# Righ_CH.net
KiCad netlist of a schematic drawn in Altium Designer
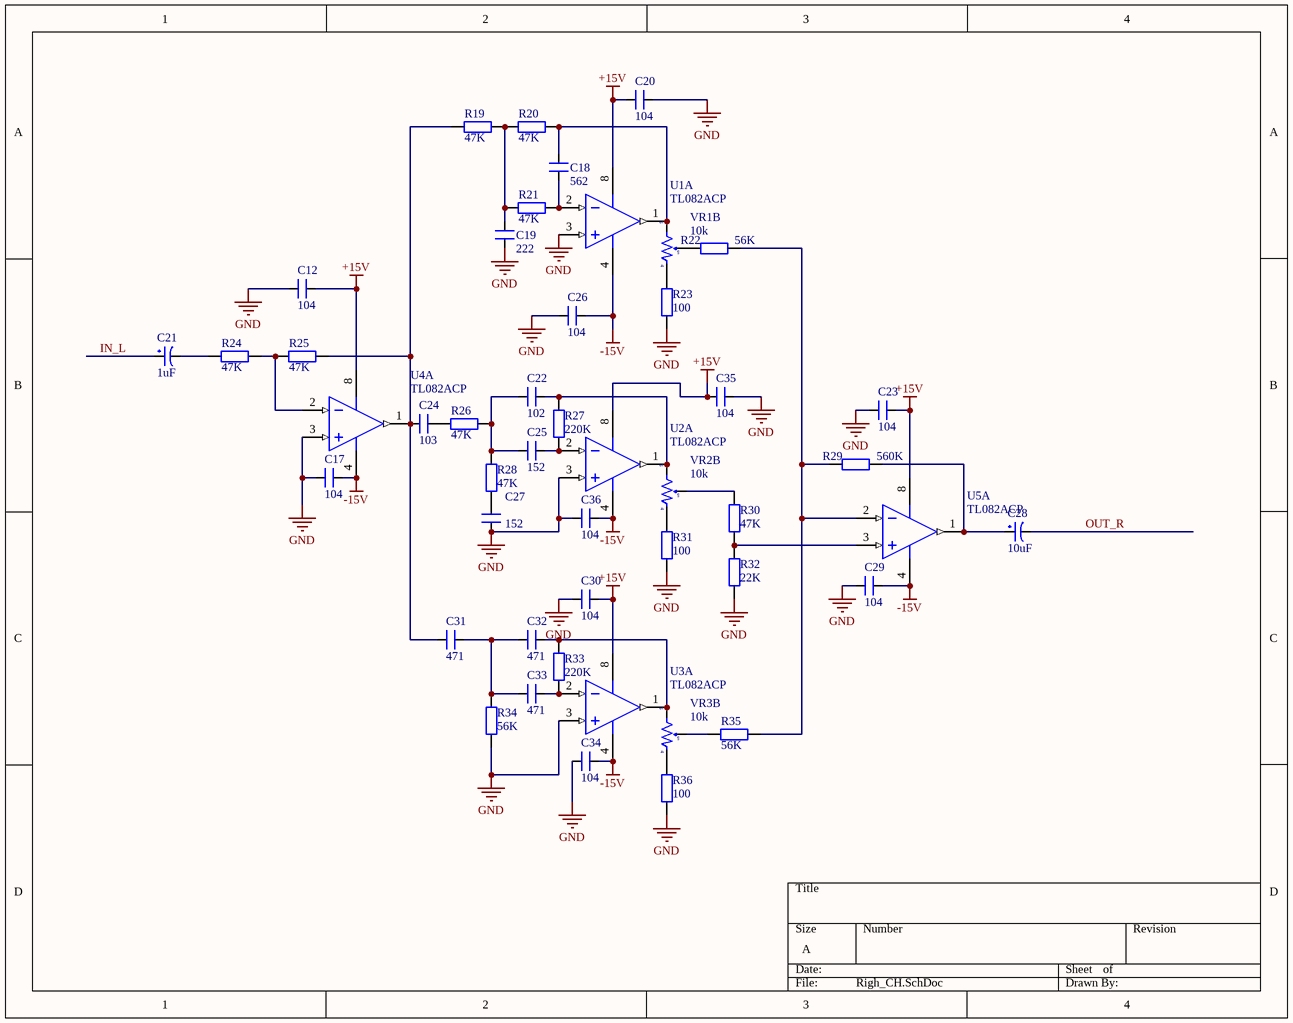
[diagram p0: Righ_CH.SchDoc]

(export (version "E")
  (design (tool "Eeschema 10.0.6"))
  (components
    (comp (ref "C12")
      (value "104")
      (footprint "TU_GOM(104-->105pF)")
      (libsource (lib "MH_DA_THU_VIEN_16122016") (part "TU_MICA_ 104 100V(2A104J)_MH"))
    )
    (comp (ref "C17")
      (value "104")
      (footprint "TU_GOM(104-->105pF)")
      (libsource (lib "MH_DA_THU_VIEN_16122016") (part "TU_MICA_ 104 100V(2A104J)_MH"))
    )
    (comp (ref "C18")
      (value "562")
      (footprint "WIMA-FKP-2-1nF")
      (libsource (lib "MH_DA_THU_VIEN_16122016") (part "TU_MICA_ 104 100V(2A104J)_MH"))
    )
    (comp (ref "C19")
      (value "222")
      (footprint "WIMA-FKP-2-1nF")
      (libsource (lib "MH_DA_THU_VIEN_16122016") (part "TU_MICA_ 104 100V(2A104J)_MH"))
    )
    (comp (ref "C20")
      (value "104")
      (footprint "TU_GOM(104-->105pF)")
      (libsource (lib "MH_DA_THU_VIEN_16122016") (part "TU_MICA_ 104 100V(2A104J)_MH"))
    )
    (comp (ref "C21")
      (value "1uF")
      (footprint "CP1/3.0")
      (description "TU_HOA_4.7uF_100V_MH")
      (libsource (lib "MH_DA_THU_VIEN_16122016") (part "TU_HOA_4.7uF_100V_MH"))
    )
    (comp (ref "C22")
      (value "102")
      (footprint "WIMA-FKP-2-1nF")
      (libsource (lib "MH_DA_THU_VIEN_16122016") (part "TU_MICA_ 104 100V(2A104J)_MH"))
    )
    (comp (ref "C23")
      (value "104")
      (footprint "TU_GOM(104-->105pF)")
      (libsource (lib "MH_DA_THU_VIEN_16122016") (part "TU_MICA_ 104 100V(2A104J)_MH"))
    )
    (comp (ref "C24")
      (value "103")
      (footprint "WIMA-FKP-2-1nF")
      (libsource (lib "MH_DA_THU_VIEN_16122016") (part "TU_MICA_ 104 100V(2A104J)_MH"))
    )
    (comp (ref "C25")
      (value "152")
      (footprint "WIMA-FKP-2-1nF")
      (libsource (lib "MH_DA_THU_VIEN_16122016") (part "TU_MICA_ 104 100V(2A104J)_MH"))
    )
    (comp (ref "C26")
      (value "104")
      (footprint "TU_GOM(104-->105pF)")
      (libsource (lib "MH_DA_THU_VIEN_16122016") (part "TU_MICA_ 104 100V(2A104J)_MH"))
    )
    (comp (ref "C27")
      (value "152")
      (footprint "WIMA-FKP-2-1nF")
      (libsource (lib "MH_DA_THU_VIEN_16122016") (part "TU_MICA_ 104 100V(2A104J)_MH"))
    )
    (comp (ref "C28")
      (value "10uF")
      (footprint "CP1/3.0")
      (description "TU_HOA_4.7uF_100V_MH")
      (libsource (lib "MH_DA_THU_VIEN_16122016") (part "TU_HOA_4.7uF_100V_MH"))
    )
    (comp (ref "C29")
      (value "104")
      (footprint "TU_GOM(104-->105pF)")
      (libsource (lib "MH_DA_THU_VIEN_16122016") (part "TU_MICA_ 104 100V(2A104J)_MH"))
    )
    (comp (ref "C30")
      (value "104")
      (footprint "TU_GOM(104-->105pF)")
      (libsource (lib "MH_DA_THU_VIEN_16122016") (part "TU_MICA_ 104 100V(2A104J)_MH"))
    )
    (comp (ref "C31")
      (value "471")
      (footprint "WIMA-FKP-2-1nF")
      (libsource (lib "MH_DA_THU_VIEN_16122016") (part "TU_MICA_ 104 100V(2A104J)_MH"))
    )
    (comp (ref "C32")
      (value "471")
      (footprint "WIMA-FKP-2-1nF")
      (libsource (lib "MH_DA_THU_VIEN_16122016") (part "TU_MICA_ 104 100V(2A104J)_MH"))
    )
    (comp (ref "C33")
      (value "471")
      (footprint "WIMA-FKP-2-1nF")
      (libsource (lib "MH_DA_THU_VIEN_16122016") (part "TU_MICA_ 104 100V(2A104J)_MH"))
    )
    (comp (ref "C34")
      (value "104")
      (footprint "TU_GOM(104-->105pF)")
      (libsource (lib "MH_DA_THU_VIEN_16122016") (part "TU_MICA_ 104 100V(2A104J)_MH"))
    )
    (comp (ref "C35")
      (value "104")
      (footprint "TU_GOM(104-->105pF)")
      (libsource (lib "MH_DA_THU_VIEN_16122016") (part "TU_MICA_ 104 100V(2A104J)_MH"))
    )
    (comp (ref "C36")
      (value "104")
      (footprint "TU_GOM(104-->105pF)")
      (libsource (lib "MH_DA_THU_VIEN_16122016") (part "TU_MICA_ 104 100V(2A104J)_MH"))
    )
    (comp (ref "R19")
      (value "47K")
      (footprint "TRO_VACH_ 1/4W")
      (description "Resistor")
      (fields (field (name "PUBLISHER") "Altium Limited"))
      (libsource (lib "") (part "TRO_VACH_1/2W_MH_2"))
    )
    (comp (ref "R20")
      (value "47K")
      (footprint "TRO_VACH_ 1/4W")
      (description "Resistor")
      (fields (field (name "PUBLISHER") "Altium Limited"))
      (libsource (lib "") (part "TRO_VACH_1/2W_MH_2"))
    )
    (comp (ref "R21")
      (value "47K")
      (footprint "TRO_VACH_ 1/4W")
      (description "Resistor")
      (fields (field (name "PUBLISHER") "Altium Limited"))
      (libsource (lib "") (part "TRO_VACH_1/2W_MH_2"))
    )
    (comp (ref "R22")
      (value "56K")
      (footprint "TRO_VACH_ 1/4W")
      (description "Resistor")
      (fields (field (name "PUBLISHER") "Altium Limited"))
      (libsource (lib "") (part "TRO_VACH_1/2W_MH_1"))
    )
    (comp (ref "R23")
      (value "100")
      (footprint "TRO_VACH_ 1/4W")
      (description "Resistor")
      (fields (field (name "PUBLISHER") "Altium Limited"))
      (libsource (lib "MH_DA_THU_VIEN_16122016") (part "TRO_VACH_1/2W_MH"))
    )
    (comp (ref "R24")
      (value "47K")
      (footprint "TRO_VACH_ 1/4W")
      (description "Resistor")
      (fields (field (name "PUBLISHER") "Altium Limited"))
      (libsource (lib "") (part "TRO_VACH_1/2W_MH_2"))
    )
    (comp (ref "R25")
      (value "47K")
      (footprint "TRO_VACH_ 1/4W")
      (description "Resistor")
      (fields (field (name "PUBLISHER") "Altium Limited"))
      (libsource (lib "") (part "TRO_VACH_1/2W_MH_2"))
    )
    (comp (ref "R26")
      (value "47K")
      (footprint "TRO_VACH_ 1/4W")
      (description "Resistor")
      (fields (field (name "PUBLISHER") "Altium Limited"))
      (libsource (lib "") (part "TRO_VACH_1/2W_MH_1"))
    )
    (comp (ref "R27")
      (value "220K")
      (footprint "TRO_VACH_ 1/4W")
      (description "Resistor")
      (fields (field (name "PUBLISHER") "Altium Limited"))
      (libsource (lib "MH_DA_THU_VIEN_16122016") (part "TRO_VACH_1/2W_MH"))
    )
    (comp (ref "R28")
      (value "47K")
      (footprint "TRO_VACH_ 1/4W")
      (description "Resistor")
      (fields (field (name "PUBLISHER") "Altium Limited"))
      (libsource (lib "MH_DA_THU_VIEN_16122016") (part "TRO_VACH_1/2W_MH"))
    )
    (comp (ref "R29")
      (value "560K")
      (footprint "TRO_VACH_ 1/4W")
      (description "Resistor")
      (fields (field (name "PUBLISHER") "Altium Limited"))
      (libsource (lib "") (part "TRO_VACH_1/2W_MH_1"))
    )
    (comp (ref "R30")
      (value "47K")
      (footprint "TRO_VACH_ 1/4W")
      (description "Resistor")
      (fields (field (name "PUBLISHER") "Altium Limited"))
      (libsource (lib "MH_DA_THU_VIEN_16122016") (part "TRO_VACH_1/2W_MH"))
    )
    (comp (ref "R31")
      (value "100")
      (footprint "TRO_VACH_ 1/4W")
      (description "Resistor")
      (fields (field (name "PUBLISHER") "Altium Limited"))
      (libsource (lib "MH_DA_THU_VIEN_16122016") (part "TRO_VACH_1/2W_MH"))
    )
    (comp (ref "R32")
      (value "22K")
      (footprint "TRO_VACH_ 1/4W")
      (description "Resistor")
      (fields (field (name "PUBLISHER") "Altium Limited"))
      (libsource (lib "MH_DA_THU_VIEN_16122016") (part "TRO_VACH_1/2W_MH"))
    )
    (comp (ref "R33")
      (value "220K")
      (footprint "TRO_VACH_ 1/4W")
      (description "Resistor")
      (fields (field (name "PUBLISHER") "Altium Limited"))
      (libsource (lib "MH_DA_THU_VIEN_16122016") (part "TRO_VACH_1/2W_MH"))
    )
    (comp (ref "R34")
      (value "56K")
      (footprint "TRO_VACH_ 1/4W")
      (description "Resistor")
      (fields (field (name "PUBLISHER") "Altium Limited"))
      (libsource (lib "MH_DA_THU_VIEN_16122016") (part "TRO_VACH_1/2W_MH"))
    )
    (comp (ref "R35")
      (value "56K")
      (footprint "TRO_VACH_ 1/4W")
      (description "Resistor")
      (fields (field (name "PUBLISHER") "Altium Limited"))
      (libsource (lib "") (part "TRO_VACH_1/2W_MH_1"))
    )
    (comp (ref "R36")
      (value "100")
      (footprint "TRO_VACH_ 1/4W")
      (description "Resistor")
      (fields (field (name "PUBLISHER") "Altium Limited"))
      (libsource (lib "MH_DA_THU_VIEN_16122016") (part "TRO_VACH_1/2W_MH"))
    )
    (comp (ref "U1")
      (value "TL082ACP")
      (footprint "DIP8")
      (description "JFET-Input Operational Amplifier")
      (fields (field (name "PUBLISHER") "Altium Limited"))
      (libsource (lib "Schlib1") (part "TL082ACP"))
    )
    (comp (ref "U2")
      (value "TL082ACP")
      (footprint "DIP8")
      (description "JFET-Input Operational Amplifier")
      (fields (field (name "PUBLISHER") "Altium Limited"))
      (libsource (lib "Schlib1") (part "TL082ACP"))
    )
    (comp (ref "U3")
      (value "TL082ACP")
      (footprint "DIP8")
      (description "JFET-Input Operational Amplifier")
      (fields (field (name "PUBLISHER") "Altium Limited"))
      (libsource (lib "Schlib1") (part "TL082ACP"))
    )
    (comp (ref "U4")
      (value "TL082ACP")
      (footprint "DIP8")
      (description "JFET-Input Operational Amplifier")
      (fields (field (name "PUBLISHER") "Altium Limited"))
      (libsource (lib "Schlib1") (part "TL082ACP"))
    )
    (comp (ref "U5")
      (value "TL082ACP")
      (footprint "DIP8")
      (description "JFET-Input Operational Amplifier")
      (fields (field (name "PUBLISHER") "Altium Limited"))
      (libsource (lib "Schlib1") (part "TL082ACP"))
    )
    (comp (ref "VR1")
      (value "10k")
      (footprint "9011")
      (description "Triet Ap Doi 10k")
      (libsource (lib "Schlib1") (part "Triet Ap Doi 10k_MH"))
    )
    (comp (ref "VR2")
      (value "10k")
      (footprint "9011")
      (description "Triet Ap Doi 10k")
      (libsource (lib "Schlib1") (part "Triet Ap Doi 10k_MH"))
    )
    (comp (ref "VR3")
      (value "10k")
      (footprint "9011")
      (description "Triet Ap Doi 10k")
      (libsource (lib "Schlib1") (part "Triet Ap Doi 10k_MH"))
    )
  )
  (nets
    (net (code "1") (name "+15V") (class "Default")
      (node (ref "C12") (pin "2") (pinfunction "2_2") (pintype "passive"))
      (node (ref "C20") (pin "1") (pinfunction "1_1") (pintype "passive"))
      (node (ref "C23") (pin "2") (pinfunction "2_2") (pintype "passive"))
      (node (ref "C30") (pin "2") (pinfunction "2_2") (pintype "passive"))
      (node (ref "C35") (pin "2") (pinfunction "2_2") (pintype "passive"))
      (node (ref "U1") (pin "8") (pinfunction "V+_8") (pintype "power_in"))
      (node (ref "U2") (pin "8") (pinfunction "V+_8") (pintype "power_in"))
      (node (ref "U3") (pin "8") (pinfunction "V+_8") (pintype "power_in"))
      (node (ref "U4") (pin "8") (pinfunction "V+_8") (pintype "power_in"))
      (node (ref "U5") (pin "8") (pinfunction "V+_8") (pintype "power_in"))
    )
    (net (code "2") (name "-15V") (class "Default")
      (node (ref "C17") (pin "2") (pinfunction "2_2") (pintype "passive"))
      (node (ref "C26") (pin "2") (pinfunction "2_2") (pintype "passive"))
      (node (ref "C29") (pin "2") (pinfunction "2_2") (pintype "passive"))
      (node (ref "C34") (pin "2") (pinfunction "2_2") (pintype "passive"))
      (node (ref "C36") (pin "1") (pinfunction "1_1") (pintype "passive"))
      (node (ref "U1") (pin "4") (pinfunction "V-_4") (pintype "power_in"))
      (node (ref "U2") (pin "4") (pinfunction "V-_4") (pintype "power_in"))
      (node (ref "U3") (pin "4") (pinfunction "V-_4") (pintype "power_in"))
      (node (ref "U4") (pin "4") (pinfunction "V-_4") (pintype "power_in"))
      (node (ref "U5") (pin "4") (pinfunction "V-_4") (pintype "power_in"))
    )
    (net (code "3") (name "/IN_L") (class "Default")
      (node (ref "C21") (pin "1") (pinfunction "1_1") (pintype "passive"))
    )
    (net (code "4") (name "/OUT_R") (class "Default")
      (node (ref "C28") (pin "2") (pinfunction "2_2") (pintype "passive"))
    )
    (net (code "5") (name "GND") (class "Default")
      (node (ref "C12") (pin "1") (pinfunction "1_1") (pintype "passive"))
      (node (ref "C17") (pin "1") (pinfunction "1_1") (pintype "passive"))
      (node (ref "C19") (pin "1") (pinfunction "1_1") (pintype "passive"))
      (node (ref "C20") (pin "2") (pinfunction "2_2") (pintype "passive"))
      (node (ref "C23") (pin "1") (pinfunction "1_1") (pintype "passive"))
      (node (ref "C26") (pin "1") (pinfunction "1_1") (pintype "passive"))
      (node (ref "C27") (pin "2") (pinfunction "2_2") (pintype "passive"))
      (node (ref "C29") (pin "1") (pinfunction "1_1") (pintype "passive"))
      (node (ref "C30") (pin "1") (pinfunction "1_1") (pintype "passive"))
      (node (ref "C34") (pin "1") (pinfunction "1_1") (pintype "passive"))
      (node (ref "C35") (pin "1") (pinfunction "1_1") (pintype "passive"))
      (node (ref "C36") (pin "2") (pinfunction "2_2") (pintype "passive"))
      (node (ref "R23") (pin "1") (pinfunction "1_1") (pintype "passive"))
      (node (ref "R31") (pin "1") (pinfunction "1_1") (pintype "passive"))
      (node (ref "R32") (pin "1") (pinfunction "1_1") (pintype "passive"))
      (node (ref "R34") (pin "1") (pinfunction "1_1") (pintype "passive"))
      (node (ref "R36") (pin "1") (pinfunction "1_1") (pintype "passive"))
      (node (ref "U1") (pin "3") (pinfunction "IN+_3") (pintype "input"))
      (node (ref "U2") (pin "3") (pinfunction "IN+_3") (pintype "input"))
      (node (ref "U3") (pin "3") (pinfunction "IN+_3") (pintype "input"))
      (node (ref "U4") (pin "3") (pinfunction "IN+_3") (pintype "input"))
    )
    (net (code "6") (name "Net-(C19-Pad2)") (class "Default")
      (node (ref "C19") (pin "2") (pinfunction "2_2") (pintype "passive"))
      (node (ref "R19") (pin "2") (pinfunction "2_2") (pintype "passive"))
      (node (ref "R20") (pin "1") (pinfunction "1_1") (pintype "passive"))
      (node (ref "R21") (pin "1") (pinfunction "1_1") (pintype "passive"))
    )
    (net (code "7") (name "Net-(C21-Pad2)") (class "Default")
      (node (ref "C21") (pin "2") (pinfunction "2_2") (pintype "passive"))
      (node (ref "R24") (pin "1") (pinfunction "1_1") (pintype "passive"))
    )
    (net (code "8") (name "Net-(C22-Pad2)") (class "Default")
      (node (ref "C22") (pin "2") (pinfunction "2_2") (pintype "passive"))
      (node (ref "C25") (pin "2") (pinfunction "2_2") (pintype "passive"))
      (node (ref "R26") (pin "1") (pinfunction "1_1") (pintype "passive"))
      (node (ref "R28") (pin "2") (pinfunction "2_2") (pintype "passive"))
    )
    (net (code "9") (name "Net-(C24-Pad2)") (class "Default")
      (node (ref "C24") (pin "2") (pinfunction "2_2") (pintype "passive"))
      (node (ref "R26") (pin "2") (pinfunction "2_2") (pintype "passive"))
    )
    (net (code "10") (name "Net-(C27-Pad1)") (class "Default")
      (node (ref "C27") (pin "1") (pinfunction "1_1") (pintype "passive"))
      (node (ref "R28") (pin "1") (pinfunction "1_1") (pintype "passive"))
    )
    (net (code "11") (name "Net-(C31-Pad1)") (class "Default")
      (node (ref "C31") (pin "1") (pinfunction "1_1") (pintype "passive"))
      (node (ref "C32") (pin "2") (pinfunction "2_2") (pintype "passive"))
      (node (ref "C33") (pin "2") (pinfunction "2_2") (pintype "passive"))
      (node (ref "R34") (pin "2") (pinfunction "2_2") (pintype "passive"))
    )
    (net (code "12") (name "Net-(R22-Pad2)") (class "Default")
      (node (ref "R22") (pin "2") (pinfunction "2_2") (pintype "passive"))
      (node (ref "VR1") (pin "5") (pinfunction "5_5") (pintype "passive"))
    )
    (net (code "13") (name "Net-(R23-Pad2)") (class "Default")
      (node (ref "R23") (pin "2") (pinfunction "2_2") (pintype "passive"))
      (node (ref "VR1") (pin "4") (pinfunction "4_4") (pintype "passive"))
    )
    (net (code "14") (name "Net-(R30-Pad2)") (class "Default")
      (node (ref "R30") (pin "2") (pinfunction "2_2") (pintype "passive"))
      (node (ref "VR2") (pin "5") (pinfunction "5_5") (pintype "passive"))
    )
    (net (code "15") (name "Net-(R31-Pad2)") (class "Default")
      (node (ref "R31") (pin "2") (pinfunction "2_2") (pintype "passive"))
      (node (ref "VR2") (pin "4") (pinfunction "4_4") (pintype "passive"))
    )
    (net (code "16") (name "Net-(R35-Pad2)") (class "Default")
      (node (ref "R35") (pin "2") (pinfunction "2_2") (pintype "passive"))
      (node (ref "VR3") (pin "5") (pinfunction "5_5") (pintype "passive"))
    )
    (net (code "17") (name "Net-(R36-Pad2)") (class "Default")
      (node (ref "R36") (pin "2") (pinfunction "2_2") (pintype "passive"))
      (node (ref "VR3") (pin "4") (pinfunction "4_4") (pintype "passive"))
    )
    (net (code "18") (name "Net-(U1A-IN-)") (class "Default")
      (node (ref "C18") (pin "1") (pinfunction "1_1") (pintype "passive"))
      (node (ref "R21") (pin "2") (pinfunction "2_2") (pintype "passive"))
      (node (ref "U1") (pin "2") (pinfunction "IN-_2") (pintype "input"))
    )
    (net (code "19") (name "Net-(U1A-OUT)") (class "Default")
      (node (ref "C18") (pin "2") (pinfunction "2_2") (pintype "passive"))
      (node (ref "R20") (pin "2") (pinfunction "2_2") (pintype "passive"))
      (node (ref "U1") (pin "1") (pinfunction "OUT_1") (pintype "output"))
      (node (ref "VR1") (pin "6") (pinfunction "6_6") (pintype "passive"))
    )
    (net (code "20") (name "Net-(U2A-IN-)") (class "Default")
      (node (ref "C25") (pin "1") (pinfunction "1_1") (pintype "passive"))
      (node (ref "R27") (pin "1") (pinfunction "1_1") (pintype "passive"))
      (node (ref "U2") (pin "2") (pinfunction "IN-_2") (pintype "input"))
    )
    (net (code "21") (name "Net-(U2A-OUT)") (class "Default")
      (node (ref "C22") (pin "1") (pinfunction "1_1") (pintype "passive"))
      (node (ref "R27") (pin "2") (pinfunction "2_2") (pintype "passive"))
      (node (ref "U2") (pin "1") (pinfunction "OUT_1") (pintype "output"))
      (node (ref "VR2") (pin "6") (pinfunction "6_6") (pintype "passive"))
    )
    (net (code "22") (name "Net-(U3A-IN-)") (class "Default")
      (node (ref "C33") (pin "1") (pinfunction "1_1") (pintype "passive"))
      (node (ref "R33") (pin "1") (pinfunction "1_1") (pintype "passive"))
      (node (ref "U3") (pin "2") (pinfunction "IN-_2") (pintype "input"))
    )
    (net (code "23") (name "Net-(U3A-OUT)") (class "Default")
      (node (ref "C32") (pin "1") (pinfunction "1_1") (pintype "passive"))
      (node (ref "R33") (pin "2") (pinfunction "2_2") (pintype "passive"))
      (node (ref "U3") (pin "1") (pinfunction "OUT_1") (pintype "output"))
      (node (ref "VR3") (pin "6") (pinfunction "6_6") (pintype "passive"))
    )
    (net (code "24") (name "Net-(U4A-IN-)") (class "Default")
      (node (ref "R24") (pin "2") (pinfunction "2_2") (pintype "passive"))
      (node (ref "R25") (pin "1") (pinfunction "1_1") (pintype "passive"))
      (node (ref "U4") (pin "2") (pinfunction "IN-_2") (pintype "input"))
    )
    (net (code "25") (name "Net-(U4A-OUT)") (class "Default")
      (node (ref "C24") (pin "1") (pinfunction "1_1") (pintype "passive"))
      (node (ref "C31") (pin "2") (pinfunction "2_2") (pintype "passive"))
      (node (ref "R19") (pin "1") (pinfunction "1_1") (pintype "passive"))
      (node (ref "R25") (pin "2") (pinfunction "2_2") (pintype "passive"))
      (node (ref "U4") (pin "1") (pinfunction "OUT_1") (pintype "output"))
    )
    (net (code "26") (name "Net-(U5A-IN+)") (class "Default")
      (node (ref "R30") (pin "1") (pinfunction "1_1") (pintype "passive"))
      (node (ref "R32") (pin "2") (pinfunction "2_2") (pintype "passive"))
      (node (ref "U5") (pin "3") (pinfunction "IN+_3") (pintype "input"))
    )
    (net (code "27") (name "Net-(U5A-IN-)") (class "Default")
      (node (ref "R22") (pin "1") (pinfunction "1_1") (pintype "passive"))
      (node (ref "R29") (pin "2") (pinfunction "2_2") (pintype "passive"))
      (node (ref "R35") (pin "1") (pinfunction "1_1") (pintype "passive"))
      (node (ref "U5") (pin "2") (pinfunction "IN-_2") (pintype "input"))
    )
    (net (code "28") (name "Net-(U5A-OUT)") (class "Default")
      (node (ref "C28") (pin "1") (pinfunction "1_1") (pintype "passive"))
      (node (ref "R29") (pin "1") (pinfunction "1_1") (pintype "passive"))
      (node (ref "U5") (pin "1") (pinfunction "OUT_1") (pintype "output"))
    )
  )
)
